# Elreg_Sender.net
KiCad netlist of a schematic drawn in Altium Designer
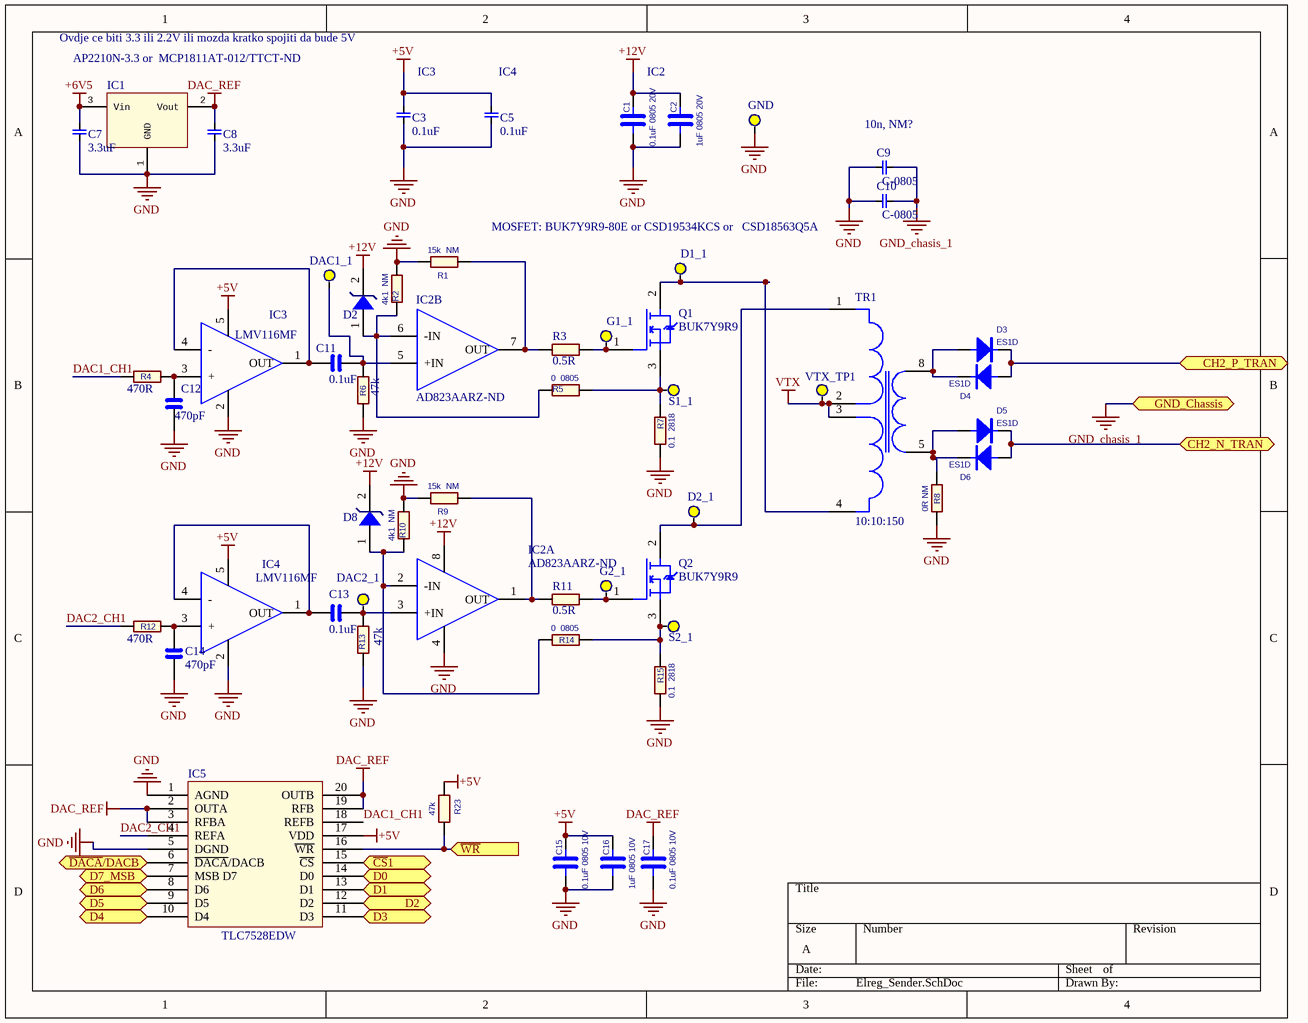
[diagram p0: Elreg_Sender.SchDoc]

(export (version "E")
  (design (tool "Eeschema 10.0.6"))
  (components
    (comp (ref "C1")
      (value "0.1uF 0805 20V")
      (footprint "C-0603")
      (description "CAP CER rrrrUF xV x% type 0805")
      (libsource (lib "Elreg (Skipper)") (part "0805CAPxxrrrrv"))
    )
    (comp (ref "C2")
      (value "1uF 0805 20V")
      (footprint "C-0603")
      (description "CAP CER rrrrUF xV x% type 0805")
      (libsource (lib "Elreg (Skipper)") (part "0805CAPxxrrrrv"))
    )
    (comp (ref "C3")
      (value "0.1uF")
      (footprint "C-0603")
      (fields (field (name "TOLERANCE") "±10%"))
      (libsource (lib "Elreg_Sender") (part "C-0805_3_3uF"))
    )
    (comp (ref "C5")
      (value "0.1uF")
      (footprint "C-0603")
      (fields (field (name "TOLERANCE") "±10%"))
      (libsource (lib "Elreg_Sender") (part "C-0805_3_3uF"))
    )
    (comp (ref "C7")
      (value "3.3uF")
      (footprint "C-0805")
      (fields (field (name "TOLERANCE") "±10%"))
      (libsource (lib "Elreg_Sender") (part "C-0805_3_3uF"))
    )
    (comp (ref "C8")
      (value "3.3uF")
      (footprint "C-0805")
      (fields (field (name "TOLERANCE") "±10%"))
      (libsource (lib "Elreg_Sender") (part "C-0805_3_3uF"))
    )
    (comp (ref "C9")
      (value "C-0805")
      (footprint "C-0805")
      (fields (field (name "TOLERANCE") "±10%"))
      (libsource (lib "Elreg_Sender") (part "C-0805"))
    )
    (comp (ref "C10")
      (value "C-0805")
      (footprint "C-0805")
      (fields (field (name "TOLERANCE") "±10%"))
      (libsource (lib "Elreg_Sender") (part "C-0805"))
    )
    (comp (ref "C11")
      (value "0.1uF")
      (footprint "C-0603")
      (description "CAP CER 0.1UF 10V X7R 0603")
      (fields (field (name "MANUFACTURER PART NUMBER") "885012206020"))
      (libsource (lib "Elreg_Sender") (part "C-0603_0_1u_10V"))
    )
    (comp (ref "C12")
      (value "470pF")
      (footprint "C-0603")
      (description "CAP CER 470p 10V C0G/NP0 0603")
      (fields (field (name "MANUFACTURER PART NUMBER") "885012006014"))
      (libsource (lib "Elreg_Sender") (part "C-0603_470p_10V"))
    )
    (comp (ref "C13")
      (value "0.1uF")
      (footprint "C-0603")
      (description "CAP CER 0.1UF 10V X7R 0603")
      (fields (field (name "MANUFACTURER PART NUMBER") "885012206020"))
      (libsource (lib "Elreg_Sender") (part "C-0603_0_1u_10V"))
    )
    (comp (ref "C14")
      (value "470pF")
      (footprint "C-0603")
      (description "CAP CER 470p 10V C0G/NP0 0603")
      (fields (field (name "MANUFACTURER PART NUMBER") "885012006014"))
      (libsource (lib "Elreg_Sender") (part "C-0603_470p_10V"))
    )
    (comp (ref "C15")
      (value "0.1uF 0805 10V")
      (footprint "C-0603")
      (description "CAP CER rrrrUF xV x% type 0805")
      (libsource (lib "Elreg (Skipper)") (part "0805CAPxxrrrrv"))
    )
    (comp (ref "C16")
      (value "1uF 0805 10V")
      (footprint "C-0603")
      (description "CAP CER rrrrUF xV x% type 0805")
      (libsource (lib "Elreg (Skipper)") (part "0805CAPxxrrrrv"))
    )
    (comp (ref "C17")
      (value "0.1uF 0805 10V")
      (footprint "C-0603")
      (description "CAP CER rrrrUF xV x% type 0805")
      (libsource (lib "Elreg (Skipper)") (part "0805CAPxxrrrrv"))
    )
    (comp (ref "D1_1")
      (value "Test_Point")
      (footprint "Test_Point")
      (libsource (lib "Elreg_Sender") (part "Test_Point"))
    )
    (comp (ref "D2")
      (value "Zener 12V")
      (footprint "DFN380P520X45-2N")
      (fields (field (name "BASE PART NUMBER") "CDBA140"))
      (libsource (lib "Elreg_Sender") (part "Zener 12V"))
    )
    (comp (ref "D2_1")
      (value "Test_Point")
      (footprint "Test_Point")
      (libsource (lib "Elreg_Sender") (part "Test_Point"))
    )
    (comp (ref "D3")
      (value "ES1D")
      (footprint "SMA")
      (description "Diode")
      (fields (field (name "MANUFACTURER") "Fairchild/ON Semiconductor"))
      (libsource (lib "Elreg_Sender") (part "ES1x"))
    )
    (comp (ref "D4")
      (value "ES1D")
      (footprint "SMA")
      (description "Diode")
      (fields (field (name "MANUFACTURER") "Fairchild/ON Semiconductor"))
      (libsource (lib "Elreg_Sender") (part "ES1x"))
    )
    (comp (ref "D5")
      (value "ES1D")
      (footprint "SMA")
      (description "Diode")
      (fields (field (name "MANUFACTURER") "Fairchild/ON Semiconductor"))
      (libsource (lib "Elreg_Sender") (part "ES1x"))
    )
    (comp (ref "D6")
      (value "ES1D")
      (footprint "SMA")
      (description "Diode")
      (fields (field (name "MANUFACTURER") "Fairchild/ON Semiconductor"))
      (libsource (lib "Elreg_Sender") (part "ES1x"))
    )
    (comp (ref "D8")
      (value "Zener 12V")
      (footprint "DFN380P520X45-2N")
      (fields (field (name "BASE PART NUMBER") "CDBA140"))
      (libsource (lib "Elreg_Sender") (part "Zener 12V"))
    )
    (comp (ref "DAC1_1")
      (value "DAC1")
      (footprint "Test_Point")
      (libsource (lib "Elreg_Sender") (part "Test_Point"))
    )
    (comp (ref "DAC2_1")
      (value "DAC2_1")
      (footprint "Test_Point")
      (libsource (lib "Elreg_Sender") (part "Test_Point"))
    )
    (comp (ref "G1_1")
      (value "Test_Point")
      (footprint "Test_Point")
      (libsource (lib "Elreg_Sender") (part "Test_Point"))
    )
    (comp (ref "G2_1")
      (value "Test_Point")
      (footprint "Test_Point")
      (libsource (lib "Elreg_Sender") (part "Test_Point"))
    )
    (comp (ref "IC1")
      (value "AP2210N-3.3 or  MCP1811AT-012/TTCT-ND")
      (footprint "SOT23-3")
      (description "AP2210N-3.3TRG1DICT-ND")
      (libsource (lib "Elreg_Sender") (part "AP2210N-3.3"))
    )
    (comp (ref "IC2")
      (value "AD823AARZ-ND")
      (footprint "TSOP65P280X110-8N")
      (description "IC OPAMP JFET 16MHZ RRO 8-MSOP")
      (libsource (lib "Elreg_Sender") (part "AD823AARZ-ND"))
    )
    (comp (ref "IC3")
      (value "LMV116MF")
      (footprint "SOT-23-5")
      (libsource (lib "Elreg_Sender") (part "LMV116MF"))
    )
    (comp (ref "IC4")
      (value "LMV116MF")
      (footprint "SOT-23-5")
      (libsource (lib "Elreg_Sender") (part "LMV116MF"))
    )
    (comp (ref "IC5")
      (value "TLC7528EDW")
      (footprint "SOIC-20")
      (libsource (lib "Elreg_Sender") (part "TLC7528EDW"))
    )
    (comp (ref "Q1")
      (value "BUK7Y9R9")
      (footprint "BUK7Y9R)")
      (libsource (lib "Elreg_Sender") (part "BUK7Y9R9"))
    )
    (comp (ref "Q2")
      (value "BUK7Y9R9")
      (footprint "BUK7Y9R)")
      (libsource (lib "Elreg_Sender") (part "BUK7Y9R9"))
    )
    (comp (ref "R1")
      (value "15k  NM")
      (footprint "R-0603")
      (description "RES xx OHM 1/8W 5% 0805 SMD")
      (libsource (lib "") (part "CRCW0805xxxxJN Default_1"))
    )
    (comp (ref "R2")
      (value "4k1  NM")
      (footprint "R-0603")
      (description "RES xx OHM 1/8W 5% 0805 SMD")
      (libsource (lib "Elreg (Skipper)") (part "CRCW0805xxxxJN Default"))
    )
    (comp (ref "R3") (value "0.5R") (footprint "R-0603") (libsource (lib "Elreg_Sender") (part "RES-0805")))
    (comp (ref "R4")
      (value "470R")
      (footprint "R-0603")
      (description "RES SMD 470 OHM 1% 0.4W 0805")
      (fields (field (name "TOLERANCE") "±5%") (field (name "MANUFACTURER PART NUMBER") "ESR10EZPF1001"))
      (libsource (lib "Elreg_Sender") (part "R-0603_470R"))
    )
    (comp (ref "R5")
      (value "0  0805")
      (footprint "R-0603")
      (description "RES xx OHM 1/8W 5% 0805 SMD")
      (libsource (lib "") (part "CRCW0805xxxxJN Default_1"))
    )
    (comp (ref "R6")
      (value "47k")
      (footprint "R-0603")
      (description "RES SMD 47k 1% 0.4W 0805")
      (fields (field (name "TOLERANCE") "±5%") (field (name "MANUFACTURER PART NUMBER") "ESR10EZPF1001"))
      (libsource (lib "") (part "R-0603_47k_1"))
    )
    (comp (ref "R7")
      (value "0.1  2818")
      (footprint "RES2818")
      (description "0.1Ohm 10W")
      (libsource (lib "") (part "CRCW0805xxxxJN Default_2"))
    )
    (comp (ref "R8")
      (value "0R NM")
      (footprint "RES-0805")
      (description "RES xx OHM 1/8W 5% 0805 SMD")
      (libsource (lib "Elreg (Skipper)") (part "CRCW0805xxxxJN Default"))
    )
    (comp (ref "R9")
      (value "15k  NM")
      (footprint "R-0603")
      (description "RES xx OHM 1/8W 5% 0805 SMD")
      (libsource (lib "") (part "CRCW0805xxxxJN Default_1"))
    )
    (comp (ref "R10")
      (value "4k1  NM")
      (footprint "R-0603")
      (description "RES xx OHM 1/8W 5% 0805 SMD")
      (libsource (lib "Elreg (Skipper)") (part "CRCW0805xxxxJN Default"))
    )
    (comp (ref "R11") (value "0.5R") (footprint "R-0603") (libsource (lib "Elreg_Sender") (part "RES-0805")))
    (comp (ref "R12")
      (value "470R")
      (footprint "R-0603")
      (description "RES SMD 470 OHM 1% 0.4W 0805")
      (fields (field (name "TOLERANCE") "±5%") (field (name "MANUFACTURER PART NUMBER") "ESR10EZPF1001"))
      (libsource (lib "Elreg_Sender") (part "R-0603_470R"))
    )
    (comp (ref "R13")
      (value "47k")
      (footprint "R-0603")
      (description "RES SMD 47k 1% 0.4W 0805")
      (fields (field (name "TOLERANCE") "±5%") (field (name "MANUFACTURER PART NUMBER") "ESR10EZPF1001"))
      (libsource (lib "Elreg_Sender") (part "R-0603_47k"))
    )
    (comp (ref "R14")
      (value "0  0805")
      (footprint "R-0603")
      (description "RES xx OHM 1/8W 5% 0805 SMD")
      (libsource (lib "") (part "CRCW0805xxxxJN Default_1"))
    )
    (comp (ref "R15")
      (value "0.1  2818")
      (footprint "RES2818")
      (description "0.1Ohm 10W")
      (libsource (lib "") (part "CRCW0805xxxxJN Default_2"))
    )
    (comp (ref "R23")
      (value "47k")
      (footprint "R-0603")
      (description "RES xx OHM 1/8W 5% 0805 SMD")
      (libsource (lib "Elreg (Skipper)") (part "CRCW0805xxxxJN Default"))
    )
    (comp (ref "S1_1")
      (value "Test_Point")
      (footprint "Test_Point")
      (libsource (lib "Elreg_Sender") (part "Test_Point"))
    )
    (comp (ref "S2_1")
      (value "Test_Point")
      (footprint "Test_Point")
      (libsource (lib "Elreg_Sender") (part "Test_Point"))
    )
    (comp (ref "TP1")
      (value "GND")
      (footprint "Test_Point")
      (libsource (lib "Elreg_Sender") (part "Test_Point"))
    )
    (comp (ref "TR1")
      (value "10:10:150")
      (footprint "Trafo_15x15")
      (libsource (lib "Elreg_Sender") (part "TRAFO_15x15"))
    )
    (comp (ref "VTX_TP1")
      (value "Test_Point")
      (footprint "Test_Point")
      (libsource (lib "Elreg_Sender") (part "Test_Point"))
    )
  )
  (nets
    (net (code "1") (name "+5V") (class "Default")
      (node (ref "C15") (pin "2") (pinfunction "2_2") (pintype "passive"))
      (node (ref "C16") (pin "2") (pinfunction "2_2") (pintype "passive"))
      (node (ref "C3") (pin "2") (pinfunction "G_2") (pintype "passive"))
      (node (ref "C5") (pin "2") (pinfunction "G_2") (pintype "passive"))
      (node (ref "IC3") (pin "5") (pinfunction "+Vs_5") (pintype "passive"))
      (node (ref "IC4") (pin "5") (pinfunction "+Vs_5") (pintype "passive"))
      (node (ref "IC5") (pin "17") (pinfunction "VDD_17") (pintype "passive"))
      (node (ref "R23") (pin "2") (pinfunction "2_2") (pintype "passive"))
    )
    (net (code "2") (name "+6V5") (class "Default")
      (node (ref "C7") (pin "2") (pinfunction "G_2") (pintype "passive"))
      (node (ref "IC1") (pin "3") (pinfunction "Vin_3") (pintype "passive"))
    )
    (net (code "3") (name "+12V") (class "Default")
      (node (ref "C1") (pin "2") (pinfunction "2_2") (pintype "passive"))
      (node (ref "C2") (pin "2") (pinfunction "2_2") (pintype "passive"))
      (node (ref "D2") (pin "2") (pinfunction "A_2") (pintype "passive"))
      (node (ref "D8") (pin "2") (pinfunction "A_2") (pintype "passive"))
      (node (ref "IC2") (pin "8") (pinfunction "+Vs_8") (pintype "passive"))
    )
    (net (code "4") (name "/CH2_N_TRAN") (class "Default")
      (node (ref "D5") (pin "2") (pinfunction "C_2") (pintype "passive"))
      (node (ref "D6") (pin "1") (pinfunction "A_1") (pintype "passive"))
    )
    (net (code "5") (name "/CH2_P_TRAN") (class "Default")
      (node (ref "D3") (pin "2") (pinfunction "C_2") (pintype "passive"))
      (node (ref "D4") (pin "1") (pinfunction "A_1") (pintype "passive"))
    )
    (net (code "6") (name "/D0") (class "Default")
      (node (ref "IC5") (pin "14") (pinfunction "D0_14") (pintype "passive"))
    )
    (net (code "7") (name "/D1") (class "Default")
      (node (ref "IC5") (pin "13") (pinfunction "D1_13") (pintype "passive"))
    )
    (net (code "8") (name "/D2") (class "Default")
      (node (ref "IC5") (pin "12") (pinfunction "D2_12") (pintype "passive"))
    )
    (net (code "9") (name "/D3") (class "Default")
      (node (ref "IC5") (pin "11") (pinfunction "D3_11") (pintype "passive"))
    )
    (net (code "10") (name "/D4") (class "Default")
      (node (ref "IC5") (pin "10") (pinfunction "D4_10") (pintype "passive"))
    )
    (net (code "11") (name "/D5") (class "Default")
      (node (ref "IC5") (pin "9") (pinfunction "D5_9") (pintype "passive"))
    )
    (net (code "12") (name "/D6") (class "Default")
      (node (ref "IC5") (pin "8") (pinfunction "D6_8") (pintype "passive"))
    )
    (net (code "13") (name "/D7_MSB") (class "Default")
      (node (ref "IC5") (pin "7") (pinfunction "MSB_D7_7") (pintype "passive"))
    )
    (net (code "14") (name "/DAC1_CH1") (class "Default")
      (node (ref "IC5") (pin "18") (pinfunction "REFB_18") (pintype "passive"))
      (node (ref "R4") (pin "1") (pinfunction "1_1") (pintype "passive"))
    )
    (net (code "15") (name "/DAC2_CH1") (class "Default")
      (node (ref "IC5") (pin "4") (pinfunction "REFA_4") (pintype "passive"))
      (node (ref "R12") (pin "1") (pinfunction "1_1") (pintype "passive"))
    )
    (net (code "16") (name "/~{CS}1") (class "Default")
      (node (ref "IC5") (pin "15") (pinfunction "~{CS}_15") (pintype "passive"))
    )
    (net (code "17") (name "/~{DACA}{slash}DACB") (class "Default")
      (node (ref "IC5") (pin "6") (pinfunction "~{DACA}/DACB_6") (pintype "passive"))
    )
    (net (code "18") (name "/~{WR}") (class "Default")
      (node (ref "IC5") (pin "16") (pinfunction "~{WR}_16") (pintype "passive"))
      (node (ref "R23") (pin "1") (pinfunction "1_1") (pintype "passive"))
    )
    (net (code "19") (name "DAC_REF") (class "Default")
      (node (ref "C17") (pin "2") (pinfunction "2_2") (pintype "passive"))
      (node (ref "C8") (pin "2") (pinfunction "G_2") (pintype "passive"))
      (node (ref "IC1") (pin "2") (pinfunction "Vout_2") (pintype "passive"))
      (node (ref "IC5") (pin "19") (pinfunction "RFB_19") (pintype "passive"))
      (node (ref "IC5") (pin "2") (pinfunction "OUTA_2") (pintype "passive"))
      (node (ref "IC5") (pin "20") (pinfunction "OUTB_20") (pintype "passive"))
      (node (ref "IC5") (pin "3") (pinfunction "RFBA_3") (pintype "passive"))
    )
    (net (code "20") (name "GND") (class "Default")
      (node (ref "C1") (pin "1") (pinfunction "1_1") (pintype "passive"))
      (node (ref "C10") (pin "1") (pinfunction "G_1") (pintype "passive"))
      (node (ref "C12") (pin "2") (pintype "passive"))
      (node (ref "C14") (pin "1") (pintype "passive"))
      (node (ref "C15") (pin "1") (pinfunction "1_1") (pintype "passive"))
      (node (ref "C16") (pin "1") (pinfunction "1_1") (pintype "passive"))
      (node (ref "C17") (pin "1") (pinfunction "1_1") (pintype "passive"))
      (node (ref "C2") (pin "1") (pinfunction "1_1") (pintype "passive"))
      (node (ref "C3") (pin "1") (pinfunction "G_1") (pintype "passive"))
      (node (ref "C5") (pin "1") (pinfunction "G_1") (pintype "passive"))
      (node (ref "C7") (pin "1") (pinfunction "G_1") (pintype "passive"))
      (node (ref "C8") (pin "1") (pinfunction "G_1") (pintype "passive"))
      (node (ref "C9") (pin "1") (pinfunction "G_1") (pintype "passive"))
      (node (ref "IC1") (pin "1") (pinfunction "GND_1") (pintype "passive"))
      (node (ref "IC2") (pin "4") (pinfunction "-Vs_4") (pintype "passive"))
      (node (ref "IC3") (pin "2") (pinfunction "-Vs_2") (pintype "passive"))
      (node (ref "IC4") (pin "2") (pinfunction "-Vs_2") (pintype "passive"))
      (node (ref "IC5") (pin "1") (pinfunction "AGND_1") (pintype "passive"))
      (node (ref "IC5") (pin "5") (pinfunction "DGND_5") (pintype "passive"))
      (node (ref "R1") (pin "1") (pinfunction "1_1") (pintype "passive"))
      (node (ref "R10") (pin "2") (pinfunction "2_2") (pintype "passive"))
      (node (ref "R13") (pin "2") (pinfunction "2_2") (pintype "passive"))
      (node (ref "R15") (pin "2") (pinfunction "2_2") (pintype "passive"))
      (node (ref "R2") (pin "2") (pinfunction "2_2") (pintype "passive"))
      (node (ref "R6") (pin "1") (pinfunction "1_1") (pintype "passive"))
      (node (ref "R7") (pin "2") (pinfunction "2_2") (pintype "passive"))
      (node (ref "R8") (pin "1") (pinfunction "1_1") (pintype "passive"))
      (node (ref "R9") (pin "1") (pinfunction "1_1") (pintype "passive"))
      (node (ref "TP1") (pin "1") (pinfunction "1_1") (pintype "passive"))
    )
    (net (code "21") (name "GND_chasis_1") (class "Default")
      (node (ref "C10") (pin "2") (pinfunction "G_2") (pintype "passive"))
      (node (ref "C9") (pin "2") (pinfunction "G_2") (pintype "passive"))
    )
    (net (code "22") (name "Net-(D1_1-Pad1)") (class "Default")
      (node (ref "D1_1") (pin "1") (pinfunction "1_1") (pintype "passive"))
      (node (ref "Q1") (pin "2") (pinfunction "G_2") (pintype "passive"))
      (node (ref "TR1") (pin "4") (pinfunction "G_4") (pintype "passive"))
    )
    (net (code "23") (name "Net-(D2_1-Pad1)") (class "Default")
      (node (ref "D2_1") (pin "1") (pinfunction "1_1") (pintype "passive"))
      (node (ref "Q2") (pin "2") (pinfunction "G_2") (pintype "passive"))
      (node (ref "TR1") (pin "1") (pinfunction "G_1") (pintype "passive"))
    )
    (net (code "24") (name "Net-(D3-A)") (class "Default")
      (node (ref "D3") (pin "1") (pinfunction "A_1") (pintype "passive"))
      (node (ref "D4") (pin "2") (pinfunction "C_2") (pintype "passive"))
      (node (ref "TR1") (pin "8") (pinfunction "G_8") (pintype "passive"))
    )
    (net (code "25") (name "Net-(D5-A)") (class "Default")
      (node (ref "D5") (pin "1") (pinfunction "A_1") (pintype "passive"))
      (node (ref "D6") (pin "2") (pinfunction "C_2") (pintype "passive"))
      (node (ref "R8") (pin "2") (pinfunction "2_2") (pintype "passive"))
      (node (ref "TR1") (pin "5") (pinfunction "G_5") (pintype "passive"))
    )
    (net (code "26") (name "Net-(G1_1-Pad1)") (class "Default")
      (node (ref "G1_1") (pin "1") (pinfunction "1_1") (pintype "passive"))
      (node (ref "Q1") (pin "1") (pinfunction "G_1") (pintype "passive"))
      (node (ref "R3") (pin "2") (pinfunction "2_2") (pintype "passive"))
    )
    (net (code "27") (name "Net-(G2_1-Pad1)") (class "Default")
      (node (ref "G2_1") (pin "1") (pinfunction "1_1") (pintype "passive"))
      (node (ref "Q2") (pin "1") (pinfunction "G_1") (pintype "passive"))
      (node (ref "R11") (pin "2") (pinfunction "2_2") (pintype "passive"))
    )
    (net (code "28") (name "Net-(IC2A-+IN)") (class "Default")
      (node (ref "C13") (pin "1") (pintype "passive"))
      (node (ref "DAC2_1") (pin "1") (pinfunction "1_1") (pintype "passive"))
      (node (ref "IC2") (pin "3") (pinfunction "+IN_3") (pintype "passive"))
      (node (ref "R13") (pin "1") (pinfunction "1_1") (pintype "passive"))
    )
    (net (code "29") (name "Net-(IC2A--IN)") (class "Default")
      (node (ref "D8") (pin "1") (pinfunction "A_1") (pintype "passive"))
      (node (ref "IC2") (pin "2") (pinfunction "-IN_2") (pintype "passive"))
      (node (ref "R10") (pin "1") (pinfunction "1_1") (pintype "passive"))
      (node (ref "R14") (pin "1") (pinfunction "1_1") (pintype "passive"))
    )
    (net (code "30") (name "Net-(IC2A-OUT)") (class "Default")
      (node (ref "IC2") (pin "1") (pinfunction "OUT_1") (pintype "passive"))
      (node (ref "R11") (pin "1") (pinfunction "1_1") (pintype "passive"))
      (node (ref "R9") (pin "2") (pinfunction "2_2") (pintype "passive"))
    )
    (net (code "31") (name "Net-(IC2B-+IN)") (class "Default")
      (node (ref "C11") (pin "1") (pintype "passive"))
      (node (ref "DAC1_1") (pin "1") (pinfunction "1_1") (pintype "passive"))
      (node (ref "IC2") (pin "5") (pinfunction "+IN_5") (pintype "passive"))
      (node (ref "R6") (pin "2") (pinfunction "2_2") (pintype "passive"))
    )
    (net (code "32") (name "Net-(IC2B--IN)") (class "Default")
      (node (ref "D2") (pin "1") (pinfunction "A_1") (pintype "passive"))
      (node (ref "IC2") (pin "6") (pinfunction "-IN_6") (pintype "passive"))
      (node (ref "R2") (pin "1") (pinfunction "1_1") (pintype "passive"))
      (node (ref "R5") (pin "1") (pinfunction "1_1") (pintype "passive"))
    )
    (net (code "33") (name "Net-(IC2B-OUT)") (class "Default")
      (node (ref "IC2") (pin "7") (pinfunction "OUT_7") (pintype "passive"))
      (node (ref "R1") (pin "2") (pinfunction "2_2") (pintype "passive"))
      (node (ref "R3") (pin "1") (pinfunction "1_1") (pintype "passive"))
    )
    (net (code "34") (name "Net-(IC3-+)") (class "Default")
      (node (ref "C12") (pin "1") (pintype "passive"))
      (node (ref "IC3") (pin "3") (pinfunction "+_3") (pintype "passive"))
      (node (ref "R4") (pin "2") (pinfunction "2_2") (pintype "passive"))
    )
    (net (code "35") (name "Net-(IC3--)") (class "Default")
      (node (ref "C11") (pin "2") (pintype "passive"))
      (node (ref "IC3") (pin "1") (pinfunction "OUT_1") (pintype "passive"))
      (node (ref "IC3") (pin "4") (pinfunction "-_4") (pintype "passive"))
    )
    (net (code "36") (name "Net-(IC4-+)") (class "Default")
      (node (ref "C14") (pin "2") (pintype "passive"))
      (node (ref "IC4") (pin "3") (pinfunction "+_3") (pintype "passive"))
      (node (ref "R12") (pin "2") (pinfunction "2_2") (pintype "passive"))
    )
    (net (code "37") (name "Net-(IC4--)") (class "Default")
      (node (ref "C13") (pin "2") (pintype "passive"))
      (node (ref "IC4") (pin "1") (pinfunction "OUT_1") (pintype "passive"))
      (node (ref "IC4") (pin "4") (pinfunction "-_4") (pintype "passive"))
    )
    (net (code "38") (name "Net-(Q1-G-Pad3)") (class "Default")
      (node (ref "Q1") (pin "3") (pinfunction "G_3") (pintype "passive"))
      (node (ref "R5") (pin "2") (pinfunction "2_2") (pintype "passive"))
      (node (ref "R7") (pin "1") (pinfunction "1_1") (pintype "passive"))
      (node (ref "S1_1") (pin "1") (pinfunction "1_1") (pintype "passive"))
    )
    (net (code "39") (name "Net-(Q2-G-Pad3)") (class "Default")
      (node (ref "Q2") (pin "3") (pinfunction "G_3") (pintype "passive"))
      (node (ref "R14") (pin "2") (pinfunction "2_2") (pintype "passive"))
      (node (ref "R15") (pin "1") (pinfunction "1_1") (pintype "passive"))
      (node (ref "S2_1") (pin "1") (pinfunction "1_1") (pintype "passive"))
    )
    (net (code "40") (name "VTX") (class "Default")
      (node (ref "TR1") (pin "2") (pinfunction "G_2") (pintype "passive"))
      (node (ref "TR1") (pin "3") (pinfunction "G_3") (pintype "passive"))
      (node (ref "VTX_TP1") (pin "1") (pinfunction "1_1") (pintype "passive"))
    )
  )
)
